# design.net
KiCad netlist of a schematic drawn in Altium Designer
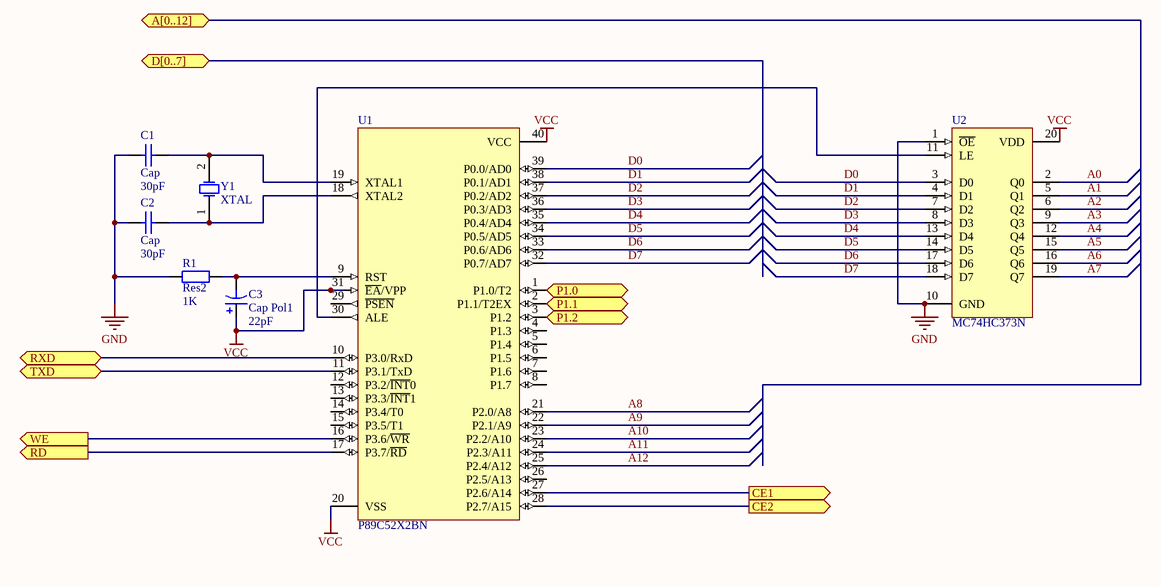
[diagram p0: 单片机原理图.SchDoc]

(export (version "E")
  (design (tool "Eeschema 10.0.6"))
  (components
    (comp (ref "C1")
      (value "Cap")
      (footprint "RAD-0.3")
      (description "Capacitor")
      (fields (field (name "ALTIUM_VALUE") "30pF") (field (name "PUBLISHER") "Altium Limited"))
      (libsource (lib "Miscellaneous Devices") (part "Cap"))
    )
    (comp (ref "C2")
      (value "Cap")
      (footprint "RAD-0.3")
      (description "Capacitor")
      (fields (field (name "ALTIUM_VALUE") "30pF") (field (name "PUBLISHER") "Altium Limited"))
      (libsource (lib "Miscellaneous Devices") (part "Cap"))
    )
    (comp (ref "C3")
      (value "Cap Pol1")
      (footprint "RB7.6-15")
      (description "Polarized Capacitor (Radial)")
      (fields (field (name "ALTIUM_VALUE") "22pF") (field (name "PUBLISHER") "Altium Limited"))
      (libsource (lib "Miscellaneous Devices") (part "Cap Pol1"))
    )
    (comp (ref "R1")
      (value "Res2")
      (footprint "AXIAL-0.4")
      (description "Resistor")
      (fields (field (name "ALTIUM_VALUE") "1K") (field (name "PUBLISHER") "Altium Limited"))
      (libsource (lib "Miscellaneous Devices") (part "Res2"))
    )
    (comp (ref "U1")
      (value "P89C52X2BN")
      (footprint "SOT129-1")
      (description "80C51 8-Bit Flash Microcontroller Family, 8 kB Flash")
      (fields (field (name "PUBLISHER") "Altium Limited"))
      (libsource (lib "Philips Microcontroller 8-Bit") (part "P89C52X2BN"))
    )
    (comp (ref "U2")
      (value "MC74HC373N")
      (footprint "738-03")
      (description "Octal 3-State Non-Inverting Transparent Latch")
      (fields (field (name "PUBLISHER") "Altium Limited"))
      (libsource (lib "Motorola Logic Latch") (part "MC74HC373N"))
    )
    (comp (ref "Y1")
      (value "XTAL")
      (footprint "R38")
      (description "Crystal Oscillator")
      (fields (field (name "PUBLISHER") "Altium Limited"))
      (libsource (lib "Miscellaneous Devices") (part "XTAL"))
    )
  )
  (nets
    (net (code "1") (name "/A0") (class "Default")
      (node (ref "U2") (pin "2") (pinfunction "Q0_2") (pintype "tri_state"))
    )
    (net (code "2") (name "/A1") (class "Default")
      (node (ref "U2") (pin "5") (pinfunction "Q1_5") (pintype "tri_state"))
    )
    (net (code "3") (name "/A2") (class "Default")
      (node (ref "U2") (pin "6") (pinfunction "Q2_6") (pintype "tri_state"))
    )
    (net (code "4") (name "/A3") (class "Default")
      (node (ref "U2") (pin "9") (pinfunction "Q3_9") (pintype "tri_state"))
    )
    (net (code "5") (name "/A4") (class "Default")
      (node (ref "U2") (pin "12") (pinfunction "Q4_12") (pintype "tri_state"))
    )
    (net (code "6") (name "/A5") (class "Default")
      (node (ref "U2") (pin "15") (pinfunction "Q5_15") (pintype "tri_state"))
    )
    (net (code "7") (name "/A6") (class "Default")
      (node (ref "U2") (pin "16") (pinfunction "Q6_16") (pintype "tri_state"))
    )
    (net (code "8") (name "/A7") (class "Default")
      (node (ref "U2") (pin "19") (pinfunction "Q7_19") (pintype "tri_state"))
    )
    (net (code "9") (name "/A8") (class "Default")
      (node (ref "U1") (pin "21") (pinfunction "P2.0/A8_21") (pintype "bidirectional"))
    )
    (net (code "10") (name "/A9") (class "Default")
      (node (ref "U1") (pin "22") (pinfunction "P2.1/A9_22") (pintype "bidirectional"))
    )
    (net (code "11") (name "/A10") (class "Default")
      (node (ref "U1") (pin "23") (pinfunction "P2.2/A10_23") (pintype "bidirectional"))
    )
    (net (code "12") (name "/A11") (class "Default")
      (node (ref "U1") (pin "24") (pinfunction "P2.3/A11_24") (pintype "bidirectional"))
    )
    (net (code "13") (name "/A12") (class "Default")
      (node (ref "U1") (pin "25") (pinfunction "P2.4/A12_25") (pintype "bidirectional"))
    )
    (net (code "15") (name "/CE1") (class "Default")
      (node (ref "U1") (pin "27") (pinfunction "P2.6/A14_27") (pintype "bidirectional"))
    )
    (net (code "16") (name "/CE2") (class "Default")
      (node (ref "U1") (pin "28") (pinfunction "P2.7/A15_28") (pintype "bidirectional"))
    )
    (net (code "17") (name "/D0") (class "Default")
      (node (ref "U1") (pin "39") (pinfunction "P0.0/AD0_39") (pintype "bidirectional"))
      (node (ref "U2") (pin "3") (pinfunction "D0_3") (pintype "input"))
    )
    (net (code "18") (name "/D1") (class "Default")
      (node (ref "U1") (pin "38") (pinfunction "P0.1/AD1_38") (pintype "bidirectional"))
      (node (ref "U2") (pin "4") (pinfunction "D1_4") (pintype "input"))
    )
    (net (code "19") (name "/D2") (class "Default")
      (node (ref "U1") (pin "37") (pinfunction "P0.2/AD2_37") (pintype "bidirectional"))
      (node (ref "U2") (pin "7") (pinfunction "D2_7") (pintype "input"))
    )
    (net (code "20") (name "/D3") (class "Default")
      (node (ref "U1") (pin "36") (pinfunction "P0.3/AD3_36") (pintype "bidirectional"))
      (node (ref "U2") (pin "8") (pinfunction "D3_8") (pintype "input"))
    )
    (net (code "21") (name "/D4") (class "Default")
      (node (ref "U1") (pin "35") (pinfunction "P0.4/AD4_35") (pintype "bidirectional"))
      (node (ref "U2") (pin "13") (pinfunction "D4_13") (pintype "input"))
    )
    (net (code "22") (name "/D5") (class "Default")
      (node (ref "U1") (pin "34") (pinfunction "P0.5/AD5_34") (pintype "bidirectional"))
      (node (ref "U2") (pin "14") (pinfunction "D5_14") (pintype "input"))
    )
    (net (code "23") (name "/D6") (class "Default")
      (node (ref "U1") (pin "33") (pinfunction "P0.6/AD6_33") (pintype "bidirectional"))
      (node (ref "U2") (pin "17") (pinfunction "D6_17") (pintype "input"))
    )
    (net (code "24") (name "/D7") (class "Default")
      (node (ref "U1") (pin "32") (pinfunction "P0.7/AD7_32") (pintype "bidirectional"))
      (node (ref "U2") (pin "18") (pinfunction "D7_18") (pintype "input"))
    )
    (net (code "26") (name "/P1.0") (class "Default")
      (node (ref "U1") (pin "1") (pinfunction "P1.0/T2_1") (pintype "bidirectional"))
    )
    (net (code "27") (name "/P1.1") (class "Default")
      (node (ref "U1") (pin "2") (pinfunction "P1.1/T2EX_2") (pintype "bidirectional"))
    )
    (net (code "28") (name "/P1.2") (class "Default")
      (node (ref "U1") (pin "3") (pinfunction "P1.2_3") (pintype "bidirectional"))
    )
    (net (code "29") (name "/RD") (class "Default")
      (node (ref "U1") (pin "17") (pinfunction "P3.7/~{RD}_17") (pintype "bidirectional"))
    )
    (net (code "30") (name "/RXD") (class "Default")
      (node (ref "U1") (pin "10") (pinfunction "P3.0/RxD_10") (pintype "bidirectional"))
    )
    (net (code "31") (name "/TXD") (class "Default")
      (node (ref "U1") (pin "11") (pinfunction "P3.1/TxD_11") (pintype "bidirectional"))
    )
    (net (code "32") (name "/WE") (class "Default")
      (node (ref "U1") (pin "16") (pinfunction "P3.6/~{WR}_16") (pintype "bidirectional"))
    )
    (net (code "33") (name "GND") (class "Default")
      (node (ref "C1") (pin "1") (pinfunction "1_1") (pintype "passive"))
      (node (ref "C2") (pin "1") (pinfunction "1_1") (pintype "passive"))
      (node (ref "R1") (pin "1") (pinfunction "1_1") (pintype "passive"))
      (node (ref "U2") (pin "1") (pinfunction "~{OE}_1") (pintype "input"))
      (node (ref "U2") (pin "10") (pinfunction "GND_10") (pintype "power_in"))
    )
    (net (code "34") (name "Net-(U1-ALE)") (class "Default")
      (node (ref "U1") (pin "30") (pinfunction "ALE_30") (pintype "output"))
      (node (ref "U2") (pin "11") (pinfunction "LE_11") (pintype "input"))
    )
    (net (code "35") (name "Net-(U1-RST)") (class "Default")
      (node (ref "C3") (pin "2") (pinfunction "2_2") (pintype "passive"))
      (node (ref "R1") (pin "2") (pinfunction "2_2") (pintype "passive"))
      (node (ref "U1") (pin "9") (pinfunction "RST_9") (pintype "input"))
    )
    (net (code "36") (name "Net-(U1-XTAL1)") (class "Default")
      (node (ref "C1") (pin "2") (pinfunction "2_2") (pintype "passive"))
      (node (ref "U1") (pin "19") (pinfunction "XTAL1_19") (pintype "input"))
      (node (ref "Y1") (pin "2") (pinfunction "OSC2_2") (pintype "passive"))
    )
    (net (code "37") (name "Net-(U1-XTAL2)") (class "Default")
      (node (ref "C2") (pin "2") (pinfunction "2_2") (pintype "passive"))
      (node (ref "U1") (pin "18") (pinfunction "XTAL2_18") (pintype "output"))
      (node (ref "Y1") (pin "1") (pinfunction "OSC1_1") (pintype "passive"))
    )
    (net (code "38") (name "VCC") (class "Default")
      (node (ref "C3") (pin "1") (pinfunction "1_1") (pintype "passive"))
      (node (ref "U1") (pin "20") (pinfunction "VSS_20") (pintype "power_in"))
      (node (ref "U1") (pin "31") (pinfunction "~{EA}/VPP_31") (pintype "input"))
      (node (ref "U1") (pin "40") (pinfunction "VCC_40") (pintype "power_in"))
      (node (ref "U2") (pin "20") (pinfunction "VDD_20") (pintype "power_in"))
    )
    (net (code "39") (name "unconnected-(U1-P1.3-Pad4)") (class "Default")
      (node (ref "U1") (pin "4") (pinfunction "P1.3_4") (pintype "bidirectional"))
    )
    (net (code "40") (name "unconnected-(U1-P1.4-Pad5)") (class "Default")
      (node (ref "U1") (pin "5") (pinfunction "P1.4_5") (pintype "bidirectional"))
    )
    (net (code "41") (name "unconnected-(U1-P1.5-Pad6)") (class "Default")
      (node (ref "U1") (pin "6") (pinfunction "P1.5_6") (pintype "bidirectional"))
    )
    (net (code "42") (name "unconnected-(U1-P1.6-Pad7)") (class "Default")
      (node (ref "U1") (pin "7") (pinfunction "P1.6_7") (pintype "bidirectional"))
    )
    (net (code "43") (name "unconnected-(U1-P1.7-Pad8)") (class "Default")
      (node (ref "U1") (pin "8") (pinfunction "P1.7_8") (pintype "bidirectional"))
    )
    (net (code "44") (name "unconnected-(U1-P2.5{slash}A13-Pad26)") (class "Default")
      (node (ref "U1") (pin "26") (pinfunction "P2.5/A13_26") (pintype "bidirectional"))
    )
    (net (code "45") (name "unconnected-(U1-P3.2{slash}~{INT}0-Pad12)") (class "Default")
      (node (ref "U1") (pin "12") (pinfunction "P3.2/~{INT}0_12") (pintype "bidirectional"))
    )
    (net (code "46") (name "unconnected-(U1-P3.3{slash}~{INT}1-Pad13)") (class "Default")
      (node (ref "U1") (pin "13") (pinfunction "P3.3/~{INT}1_13") (pintype "bidirectional"))
    )
    (net (code "47") (name "unconnected-(U1-P3.4{slash}T0-Pad14)") (class "Default")
      (node (ref "U1") (pin "14") (pinfunction "P3.4/T0_14") (pintype "bidirectional"))
    )
    (net (code "48") (name "unconnected-(U1-P3.5{slash}T1-Pad15)") (class "Default")
      (node (ref "U1") (pin "15") (pinfunction "P3.5/T1_15") (pintype "bidirectional"))
    )
    (net (code "49") (name "unconnected-(U1-~{PSEN}-Pad29)") (class "Default")
      (node (ref "U1") (pin "29") (pinfunction "~{PSEN}_29") (pintype "output"))
    )
  )
)
